# Mcu.net
KiCad netlist of a schematic drawn in Altium Designer
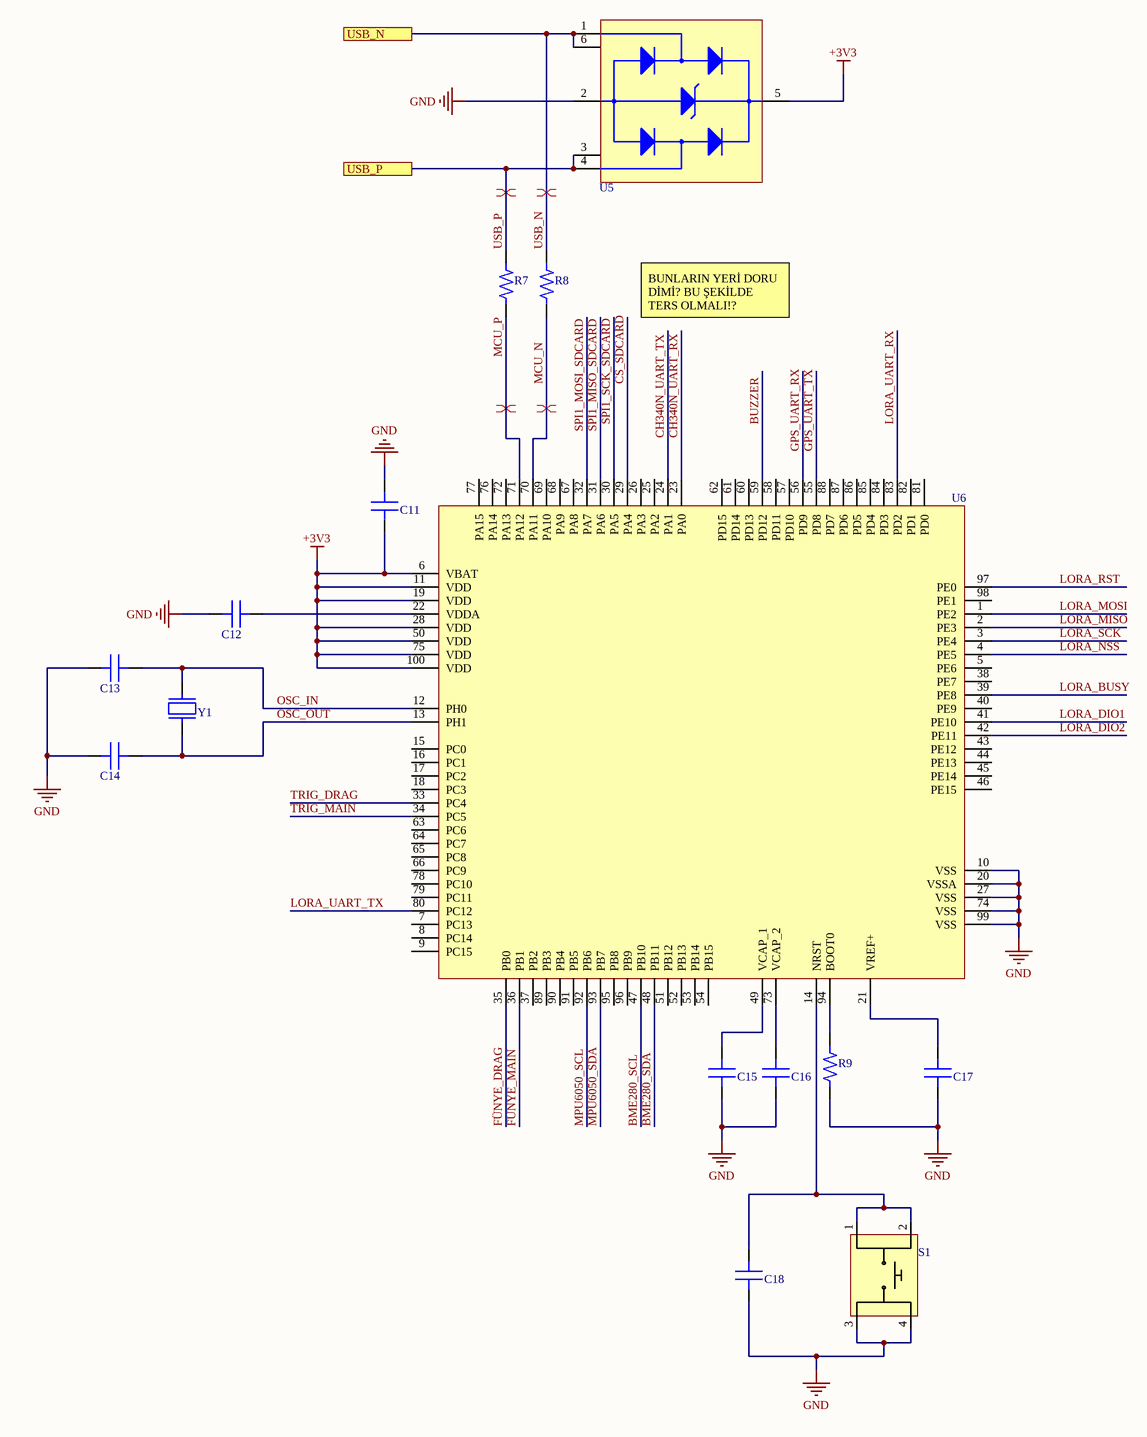
[diagram p0: Mcu.SchDoc]

(export (version "E")
  (design (tool "Eeschema 10.0.6"))
  (components
    (comp (ref "C11")
      (value "CAP CER 1uF 0805")
      (footprint "CAP_0805")
      (libsource (lib "ROKET_LIBRARY") (part "CAP CER 1uF 0805"))
    )
    (comp (ref "C12")
      (value "CAP CER 10nF 0805")
      (footprint "CAP_0805")
      (libsource (lib "ROKET_LIBRARY") (part "CAP CER 10nF 0805"))
    )
    (comp (ref "C13")
      (value "CAP CER 20pF 0805")
      (footprint "CAP_0805")
      (libsource (lib "ROKET_LIBRARY") (part "CAP CER 20pF 0805"))
    )
    (comp (ref "C14")
      (value "CAP CER 20pF 0805")
      (footprint "CAP_0805")
      (libsource (lib "ROKET_LIBRARY") (part "CAP CER 20pF 0805"))
    )
    (comp (ref "C15")
      (value "CAP CER 2.2uF 0805")
      (footprint "CAP_0805")
      (libsource (lib "ROKET_LIBRARY") (part "CAP CER 2.2uF 0805"))
    )
    (comp (ref "C16")
      (value "CAP CER 2.2uF 0805")
      (footprint "CAP_0805")
      (libsource (lib "ROKET_LIBRARY") (part "CAP CER 2.2uF 0805"))
    )
    (comp (ref "C17")
      (value "CAP CER 10nF 0805")
      (footprint "CAP_0805")
      (libsource (lib "ROKET_LIBRARY") (part "CAP CER 10nF 0805"))
    )
    (comp (ref "C18")
      (value "CAP CER 0.1uF 0805")
      (footprint "CAP_0805")
      (libsource (lib "ROKET_LIBRARY") (part "CAP CER 0.1uF 0805"))
    )
    (comp (ref "R7")
      (value "RES 15 OHM 0805")
      (footprint "RES_0805")
      (libsource (lib "ROKET_LIBRARY") (part "RES 15 OHM 0805"))
    )
    (comp (ref "R8")
      (value "RES 15 OHM 0805")
      (footprint "RES_0805")
      (libsource (lib "ROKET_LIBRARY") (part "RES 15 OHM 0805"))
    )
    (comp (ref "R9")
      (value "RES 10K OHM 0805")
      (footprint "RES_0805")
      (libsource (lib "ROKET_LIBRARY") (part "RES 10K OHM 0805"))
    )
    (comp (ref "S1")
      (value "PTS815 SJG 250 SMTR LFS")
      (footprint "BUTTON")
      (description "Switch Tactile N.O. SPST Button J-Bend 0.05A 12VDC 3.92N SMD T/R")
      (fields
        (field (name "MANUFACTURER") "ITT C&K")
        (field (name "MANUFACTURER PART NUMBER") "PTS815SJG250SMTRLFS")
      )
      (libsource (lib "ROKET_LIBRARY") (part "BUTTON"))
    )
    (comp (ref "U5")
      (value "USBLC6-2SC6")
      (footprint "SOT-23-6L")
      (description "TVS DIODE 5.25VWM 17VC SOT23-6")
      (fields (field (name "MANUFACTURER") "STMicroelectronics"))
      (libsource (lib "ROKET_LIBRARY") (part "USB PROTECTION"))
    )
    (comp (ref "U6")
      (value "STM32F407VGT6")
      (footprint "LQFP-100")
      (description "IC MCU 32BIT 1MB FLASH 100LQFP")
      (fields (field (name "MANUFACTURER") "STMicroelectronics"))
      (libsource (lib "ROKET_LIBRARY") (part "STM32F407VGT6"))
    )
    (comp (ref "Y1")
      (value "CRYSTAL 32.7680KHZ 12.5PF SMD")
      (footprint "CRYSTAL_ABS05")
      (description "Crystal 0.032768MHz ±20ppm (Tol) 12.5pF Flexural 90000Ohm 2-Pin CSMD T/R")
      (fields
        (field (name "MANUFACTURER") "Abracon")
        (field (name "MANUFACTURER PART NUMBER") "ABS05-32.768KHZ-T")
      )
      (libsource (lib "ROKET_LIBRARY") (part "CRYSTAL"))
    )
  )
  (nets
    (net (code "1") (name "+3V3") (class "Default")
      (node (ref "C11") (pin "1") (pinfunction "1_1") (pintype "passive"))
      (node (ref "U5") (pin "5") (pinfunction "VBUS_5") (pintype "power_in"))
      (node (ref "U6") (pin "100") (pinfunction "VDD_100") (pintype "passive"))
      (node (ref "U6") (pin "11") (pinfunction "VDD_11") (pintype "passive"))
      (node (ref "U6") (pin "19") (pinfunction "VDD_19") (pintype "passive"))
      (node (ref "U6") (pin "28") (pinfunction "VDD_28") (pintype "passive"))
      (node (ref "U6") (pin "50") (pinfunction "VDD_50") (pintype "passive"))
      (node (ref "U6") (pin "6") (pinfunction "VBAT_6") (pintype "passive"))
      (node (ref "U6") (pin "75") (pinfunction "VDD_75") (pintype "passive"))
    )
    (net (code "2") (name "/BME280_SCL") (class "Default")
      (node (ref "U6") (pin "47") (pinfunction "PB10_47") (pintype "passive"))
    )
    (net (code "3") (name "/BME280_SDA") (class "Default")
      (node (ref "U6") (pin "48") (pinfunction "PB11_48") (pintype "passive"))
    )
    (net (code "4") (name "/BUZZER") (class "Default")
      (node (ref "U6") (pin "59") (pinfunction "PD12_59") (pintype "passive"))
    )
    (net (code "5") (name "/CH340N_UART_RX") (class "Default")
      (node (ref "U6") (pin "23") (pinfunction "PA0_23") (pintype "passive"))
    )
    (net (code "6") (name "/CH340N_UART_TX") (class "Default")
      (node (ref "U6") (pin "24") (pinfunction "PA1_24") (pintype "passive"))
    )
    (net (code "7") (name "/CS_SDCARD") (class "Default")
      (node (ref "U6") (pin "29") (pinfunction "PA4_29") (pintype "passive"))
    )
    (net (code "8") (name "/FÜNYE_DRAG") (class "Default")
      (node (ref "U6") (pin "35") (pinfunction "PB0_35") (pintype "passive"))
    )
    (net (code "9") (name "/FÜNYE_MAIN") (class "Default")
      (node (ref "U6") (pin "36") (pinfunction "PB1_36") (pintype "passive"))
    )
    (net (code "10") (name "/GPS_UART_RX") (class "Default")
      (node (ref "U6") (pin "56") (pinfunction "PD9_56") (pintype "passive"))
    )
    (net (code "11") (name "/GPS_UART_TX") (class "Default")
      (node (ref "U6") (pin "55") (pinfunction "PD8_55") (pintype "passive"))
    )
    (net (code "12") (name "/LORA_BUSY") (class "Default")
      (node (ref "U6") (pin "39") (pinfunction "PE8_39") (pintype "passive"))
    )
    (net (code "13") (name "/LORA_DIO1") (class "Default")
      (node (ref "U6") (pin "41") (pinfunction "PE10_41") (pintype "passive"))
    )
    (net (code "14") (name "/LORA_DIO2") (class "Default")
      (node (ref "U6") (pin "42") (pinfunction "PE11_42") (pintype "passive"))
    )
    (net (code "15") (name "/LORA_MISO") (class "Default")
      (node (ref "U6") (pin "2") (pinfunction "PE3_2") (pintype "passive"))
    )
    (net (code "16") (name "/LORA_MOSI") (class "Default")
      (node (ref "U6") (pin "1") (pinfunction "PE2_1") (pintype "passive"))
    )
    (net (code "17") (name "/LORA_NSS") (class "Default")
      (node (ref "U6") (pin "4") (pinfunction "PE5_4") (pintype "passive"))
    )
    (net (code "18") (name "/LORA_RST") (class "Default")
      (node (ref "U6") (pin "97") (pinfunction "PE0_97") (pintype "passive"))
    )
    (net (code "19") (name "/LORA_SCK") (class "Default")
      (node (ref "U6") (pin "3") (pinfunction "PE4_3") (pintype "passive"))
    )
    (net (code "20") (name "/LORA_UART_RX") (class "Default")
      (node (ref "U6") (pin "83") (pinfunction "PD2_83") (pintype "passive"))
    )
    (net (code "21") (name "/LORA_UART_TX") (class "Default")
      (node (ref "U6") (pin "80") (pinfunction "PC12_80") (pintype "passive"))
    )
    (net (code "22") (name "/MCU_N") (class "Default")
      (node (ref "R8") (pin "1") (pinfunction "1_1") (pintype "passive"))
      (node (ref "U6") (pin "70") (pinfunction "PA11_70") (pintype "passive"))
    )
    (net (code "23") (name "/MCU_P") (class "Default")
      (node (ref "R7") (pin "1") (pinfunction "1_1") (pintype "passive"))
      (node (ref "U6") (pin "71") (pinfunction "PA12_71") (pintype "passive"))
    )
    (net (code "24") (name "/MPU6050_SCL") (class "Default")
      (node (ref "U6") (pin "92") (pinfunction "PB6_92") (pintype "passive"))
    )
    (net (code "25") (name "/MPU6050_SDA") (class "Default")
      (node (ref "U6") (pin "93") (pinfunction "PB7_93") (pintype "passive"))
    )
    (net (code "26") (name "/OSC_IN") (class "Default")
      (node (ref "C13") (pin "2") (pinfunction "2_2") (pintype "passive"))
      (node (ref "U6") (pin "12") (pinfunction "PH0_12") (pintype "passive"))
      (node (ref "Y1") (pin "2") (pinfunction "2_2") (pintype "passive"))
    )
    (net (code "27") (name "/OSC_OUT") (class "Default")
      (node (ref "C14") (pin "2") (pinfunction "2_2") (pintype "passive"))
      (node (ref "U6") (pin "13") (pinfunction "PH1_13") (pintype "passive"))
      (node (ref "Y1") (pin "1") (pinfunction "1_1") (pintype "passive"))
    )
    (net (code "28") (name "/SPI1_MISO_SDCARD") (class "Default")
      (node (ref "U6") (pin "31") (pinfunction "PA6_31") (pintype "passive"))
    )
    (net (code "29") (name "/SPI1_MOSI_SDCARD") (class "Default")
      (node (ref "U6") (pin "32") (pinfunction "PA7_32") (pintype "passive"))
    )
    (net (code "30") (name "/SPI1_SCK_SDCARD") (class "Default")
      (node (ref "U6") (pin "30") (pinfunction "PA5_30") (pintype "passive"))
    )
    (net (code "31") (name "/TRIG_DRAG") (class "Default")
      (node (ref "U6") (pin "33") (pinfunction "PC4_33") (pintype "passive"))
    )
    (net (code "32") (name "/TRIG_MAIN") (class "Default")
      (node (ref "U6") (pin "34") (pinfunction "PC5_34") (pintype "passive"))
    )
    (net (code "33") (name "/USB_N") (class "Default")
      (node (ref "R8") (pin "2") (pinfunction "2_2") (pintype "passive"))
      (node (ref "U5") (pin "1") (pinfunction "I/O1_IN_1") (pintype "passive"))
      (node (ref "U5") (pin "6") (pinfunction "I/O1_OUT_6") (pintype "passive"))
    )
    (net (code "34") (name "/USB_P") (class "Default")
      (node (ref "R7") (pin "2") (pinfunction "2_2") (pintype "passive"))
      (node (ref "U5") (pin "3") (pinfunction "I/O2_IN_3") (pintype "passive"))
      (node (ref "U5") (pin "4") (pinfunction "I/O2_OUT_4") (pintype "passive"))
    )
    (net (code "35") (name "GND") (class "Default")
      (node (ref "C11") (pin "2") (pinfunction "2_2") (pintype "passive"))
      (node (ref "C12") (pin "1") (pinfunction "1_1") (pintype "passive"))
      (node (ref "C13") (pin "1") (pinfunction "1_1") (pintype "passive"))
      (node (ref "C14") (pin "1") (pinfunction "1_1") (pintype "passive"))
      (node (ref "C15") (pin "1") (pinfunction "1_1") (pintype "passive"))
      (node (ref "C16") (pin "1") (pinfunction "1_1") (pintype "passive"))
      (node (ref "C17") (pin "1") (pinfunction "1_1") (pintype "passive"))
      (node (ref "C18") (pin "1") (pinfunction "1_1") (pintype "passive"))
      (node (ref "R9") (pin "1") (pinfunction "1_1") (pintype "passive"))
      (node (ref "S1") (pin "3") (pinfunction "3_3") (pintype "passive"))
      (node (ref "S1") (pin "4") (pinfunction "4_4") (pintype "passive"))
      (node (ref "U5") (pin "2") (pinfunction "GND_2") (pintype "power_in"))
      (node (ref "U6") (pin "10") (pinfunction "VSS_10") (pintype "passive"))
      (node (ref "U6") (pin "20") (pinfunction "VSSA_20") (pintype "passive"))
      (node (ref "U6") (pin "27") (pinfunction "VSS_27") (pintype "passive"))
      (node (ref "U6") (pin "74") (pinfunction "VSS_74") (pintype "passive"))
      (node (ref "U6") (pin "99") (pinfunction "VSS_99") (pintype "passive"))
    )
    (net (code "36") (name "Net-(U6-BOOT0)") (class "Default")
      (node (ref "R9") (pin "2") (pinfunction "2_2") (pintype "passive"))
      (node (ref "U6") (pin "94") (pinfunction "BOOT0_94") (pintype "passive"))
    )
    (net (code "37") (name "Net-(U6-NRST)") (class "Default")
      (node (ref "C18") (pin "2") (pinfunction "2_2") (pintype "passive"))
      (node (ref "S1") (pin "1") (pinfunction "1_1") (pintype "passive"))
      (node (ref "S1") (pin "2") (pinfunction "2_2") (pintype "passive"))
      (node (ref "U6") (pin "14") (pinfunction "NRST_14") (pintype "passive"))
    )
    (net (code "38") (name "Net-(U6-VCAP_1)") (class "Default")
      (node (ref "C15") (pin "2") (pinfunction "2_2") (pintype "passive"))
      (node (ref "U6") (pin "49") (pinfunction "VCAP_1_49") (pintype "passive"))
    )
    (net (code "39") (name "Net-(U6-VCAP_2)") (class "Default")
      (node (ref "C16") (pin "2") (pinfunction "2_2") (pintype "passive"))
      (node (ref "U6") (pin "73") (pinfunction "VCAP_2_73") (pintype "passive"))
    )
    (net (code "40") (name "Net-(U6-VDDA)") (class "Default")
      (node (ref "C12") (pin "2") (pinfunction "2_2") (pintype "passive"))
      (node (ref "U6") (pin "22") (pinfunction "VDDA_22") (pintype "passive"))
    )
    (net (code "41") (name "Net-(U6-VREF+)") (class "Default")
      (node (ref "C17") (pin "2") (pinfunction "2_2") (pintype "passive"))
      (node (ref "U6") (pin "21") (pinfunction "VREF+_21") (pintype "passive"))
    )
    (net (code "42") (name "unconnected-(U6-PA2-Pad25)") (class "Default")
      (node (ref "U6") (pin "25") (pinfunction "PA2_25") (pintype "passive"))
    )
    (net (code "43") (name "unconnected-(U6-PA3-Pad26)") (class "Default")
      (node (ref "U6") (pin "26") (pinfunction "PA3_26") (pintype "passive"))
    )
    (net (code "44") (name "unconnected-(U6-PA8-Pad67)") (class "Default")
      (node (ref "U6") (pin "67") (pinfunction "PA8_67") (pintype "passive"))
    )
    (net (code "45") (name "unconnected-(U6-PA9-Pad68)") (class "Default")
      (node (ref "U6") (pin "68") (pinfunction "PA9_68") (pintype "passive"))
    )
    (net (code "46") (name "unconnected-(U6-PA10-Pad69)") (class "Default")
      (node (ref "U6") (pin "69") (pinfunction "PA10_69") (pintype "passive"))
    )
    (net (code "47") (name "unconnected-(U6-PA13-Pad72)") (class "Default")
      (node (ref "U6") (pin "72") (pinfunction "PA13_72") (pintype "passive"))
    )
    (net (code "48") (name "unconnected-(U6-PA14-Pad76)") (class "Default")
      (node (ref "U6") (pin "76") (pinfunction "PA14_76") (pintype "passive"))
    )
    (net (code "49") (name "unconnected-(U6-PA15-Pad77)") (class "Default")
      (node (ref "U6") (pin "77") (pinfunction "PA15_77") (pintype "passive"))
    )
    (net (code "50") (name "unconnected-(U6-PB2-Pad37)") (class "Default")
      (node (ref "U6") (pin "37") (pinfunction "PB2_37") (pintype "passive"))
    )
    (net (code "51") (name "unconnected-(U6-PB3-Pad89)") (class "Default")
      (node (ref "U6") (pin "89") (pinfunction "PB3_89") (pintype "passive"))
    )
    (net (code "52") (name "unconnected-(U6-PB4-Pad90)") (class "Default")
      (node (ref "U6") (pin "90") (pinfunction "PB4_90") (pintype "passive"))
    )
    (net (code "53") (name "unconnected-(U6-PB5-Pad91)") (class "Default")
      (node (ref "U6") (pin "91") (pinfunction "PB5_91") (pintype "passive"))
    )
    (net (code "54") (name "unconnected-(U6-PB8-Pad95)") (class "Default")
      (node (ref "U6") (pin "95") (pinfunction "PB8_95") (pintype "passive"))
    )
    (net (code "55") (name "unconnected-(U6-PB9-Pad96)") (class "Default")
      (node (ref "U6") (pin "96") (pinfunction "PB9_96") (pintype "passive"))
    )
    (net (code "56") (name "unconnected-(U6-PB12-Pad51)") (class "Default")
      (node (ref "U6") (pin "51") (pinfunction "PB12_51") (pintype "passive"))
    )
    (net (code "57") (name "unconnected-(U6-PB13-Pad52)") (class "Default")
      (node (ref "U6") (pin "52") (pinfunction "PB13_52") (pintype "passive"))
    )
    (net (code "58") (name "unconnected-(U6-PB14-Pad53)") (class "Default")
      (node (ref "U6") (pin "53") (pinfunction "PB14_53") (pintype "passive"))
    )
    (net (code "59") (name "unconnected-(U6-PB15-Pad54)") (class "Default")
      (node (ref "U6") (pin "54") (pinfunction "PB15_54") (pintype "passive"))
    )
    (net (code "60") (name "unconnected-(U6-PC0-Pad15)") (class "Default")
      (node (ref "U6") (pin "15") (pinfunction "PC0_15") (pintype "passive"))
    )
    (net (code "61") (name "unconnected-(U6-PC1-Pad16)") (class "Default")
      (node (ref "U6") (pin "16") (pinfunction "PC1_16") (pintype "passive"))
    )
    (net (code "62") (name "unconnected-(U6-PC2-Pad17)") (class "Default")
      (node (ref "U6") (pin "17") (pinfunction "PC2_17") (pintype "passive"))
    )
    (net (code "63") (name "unconnected-(U6-PC3-Pad18)") (class "Default")
      (node (ref "U6") (pin "18") (pinfunction "PC3_18") (pintype "passive"))
    )
    (net (code "64") (name "unconnected-(U6-PC6-Pad63)") (class "Default")
      (node (ref "U6") (pin "63") (pinfunction "PC6_63") (pintype "passive"))
    )
    (net (code "65") (name "unconnected-(U6-PC7-Pad64)") (class "Default")
      (node (ref "U6") (pin "64") (pinfunction "PC7_64") (pintype "passive"))
    )
    (net (code "66") (name "unconnected-(U6-PC8-Pad65)") (class "Default")
      (node (ref "U6") (pin "65") (pinfunction "PC8_65") (pintype "passive"))
    )
    (net (code "67") (name "unconnected-(U6-PC9-Pad66)") (class "Default")
      (node (ref "U6") (pin "66") (pinfunction "PC9_66") (pintype "passive"))
    )
    (net (code "68") (name "unconnected-(U6-PC10-Pad78)") (class "Default")
      (node (ref "U6") (pin "78") (pinfunction "PC10_78") (pintype "passive"))
    )
    (net (code "69") (name "unconnected-(U6-PC11-Pad79)") (class "Default")
      (node (ref "U6") (pin "79") (pinfunction "PC11_79") (pintype "passive"))
    )
    (net (code "70") (name "unconnected-(U6-PC13-Pad7)") (class "Default")
      (node (ref "U6") (pin "7") (pinfunction "PC13_7") (pintype "passive"))
    )
    (net (code "71") (name "unconnected-(U6-PC14-Pad8)") (class "Default")
      (node (ref "U6") (pin "8") (pinfunction "PC14_8") (pintype "passive"))
    )
    (net (code "72") (name "unconnected-(U6-PC15-Pad9)") (class "Default")
      (node (ref "U6") (pin "9") (pinfunction "PC15_9") (pintype "passive"))
    )
    (net (code "73") (name "unconnected-(U6-PD0-Pad81)") (class "Default")
      (node (ref "U6") (pin "81") (pinfunction "PD0_81") (pintype "passive"))
    )
    (net (code "74") (name "unconnected-(U6-PD1-Pad82)") (class "Default")
      (node (ref "U6") (pin "82") (pinfunction "PD1_82") (pintype "passive"))
    )
    (net (code "75") (name "unconnected-(U6-PD3-Pad84)") (class "Default")
      (node (ref "U6") (pin "84") (pinfunction "PD3_84") (pintype "passive"))
    )
    (net (code "76") (name "unconnected-(U6-PD4-Pad85)") (class "Default")
      (node (ref "U6") (pin "85") (pinfunction "PD4_85") (pintype "passive"))
    )
    (net (code "77") (name "unconnected-(U6-PD5-Pad86)") (class "Default")
      (node (ref "U6") (pin "86") (pinfunction "PD5_86") (pintype "passive"))
    )
    (net (code "78") (name "unconnected-(U6-PD6-Pad87)") (class "Default")
      (node (ref "U6") (pin "87") (pinfunction "PD6_87") (pintype "passive"))
    )
    (net (code "79") (name "unconnected-(U6-PD7-Pad88)") (class "Default")
      (node (ref "U6") (pin "88") (pinfunction "PD7_88") (pintype "passive"))
    )
    (net (code "80") (name "unconnected-(U6-PD10-Pad57)") (class "Default")
      (node (ref "U6") (pin "57") (pinfunction "PD10_57") (pintype "passive"))
    )
    (net (code "81") (name "unconnected-(U6-PD11-Pad58)") (class "Default")
      (node (ref "U6") (pin "58") (pinfunction "PD11_58") (pintype "passive"))
    )
    (net (code "82") (name "unconnected-(U6-PD13-Pad60)") (class "Default")
      (node (ref "U6") (pin "60") (pinfunction "PD13_60") (pintype "passive"))
    )
    (net (code "83") (name "unconnected-(U6-PD14-Pad61)") (class "Default")
      (node (ref "U6") (pin "61") (pinfunction "PD14_61") (pintype "passive"))
    )
    (net (code "84") (name "unconnected-(U6-PD15-Pad62)") (class "Default")
      (node (ref "U6") (pin "62") (pinfunction "PD15_62") (pintype "passive"))
    )
    (net (code "85") (name "unconnected-(U6-PE1-Pad98)") (class "Default")
      (node (ref "U6") (pin "98") (pinfunction "PE1_98") (pintype "passive"))
    )
    (net (code "86") (name "unconnected-(U6-PE6-Pad5)") (class "Default")
      (node (ref "U6") (pin "5") (pinfunction "PE6_5") (pintype "passive"))
    )
    (net (code "87") (name "unconnected-(U6-PE7-Pad38)") (class "Default")
      (node (ref "U6") (pin "38") (pinfunction "PE7_38") (pintype "passive"))
    )
    (net (code "88") (name "unconnected-(U6-PE9-Pad40)") (class "Default")
      (node (ref "U6") (pin "40") (pinfunction "PE9_40") (pintype "passive"))
    )
    (net (code "89") (name "unconnected-(U6-PE12-Pad43)") (class "Default")
      (node (ref "U6") (pin "43") (pinfunction "PE12_43") (pintype "passive"))
    )
    (net (code "90") (name "unconnected-(U6-PE13-Pad44)") (class "Default")
      (node (ref "U6") (pin "44") (pinfunction "PE13_44") (pintype "passive"))
    )
    (net (code "91") (name "unconnected-(U6-PE14-Pad45)") (class "Default")
      (node (ref "U6") (pin "45") (pinfunction "PE14_45") (pintype "passive"))
    )
    (net (code "92") (name "unconnected-(U6-PE15-Pad46)") (class "Default")
      (node (ref "U6") (pin "46") (pinfunction "PE15_46") (pintype "passive"))
    )
  )
)
